# LCD_Schem.net
KiCad netlist of a schematic drawn in Altium Designer
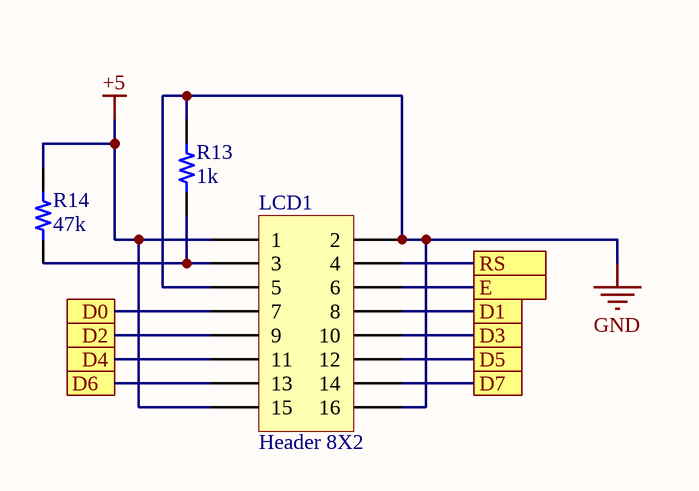
[diagram p0: LCD_Schem.SchDoc]

(export (version "E")
  (design (tool "Eeschema 10.0.6"))
  (components
    (comp (ref "LCD1")
      (value "Header 8X2")
      (footprint "HDR2X8")
      (description "Header, 8-Pin, Dual row")
      (fields (field (name "PUBLISHER") "Altium Limited"))
      (libsource (lib "Miscellaneous Connectors") (part "Header 8X2"))
    )
    (comp (ref "R13")
      (value "1k")
      (footprint "RES 1206_3216")
      (description "RES SMD 10K OHM 1% 1/2W 1206")
      (fields (field (name "PART NUMBER") "ESR18EZPF1002") (field (name "MANUFACTURER") "Rohm Semiconductor"))
      (libsource (lib "Celestial Altium Library - altium_library") (part "Resistor"))
    )
    (comp (ref "R14")
      (value "47k")
      (footprint "RES 1206_3216")
      (description "RES SMD 10K OHM 1% 1/2W 1206")
      (fields (field (name "PART NUMBER") "ESR18EZPF1002") (field (name "MANUFACTURER") "Rohm Semiconductor"))
      (libsource (lib "Celestial Altium Library - altium_library") (part "Resistor"))
    )
  )
  (nets
    (net (code "1") (name "+5") (class "Default")
      (node (ref "LCD1") (pin "1") (pinfunction "1_1") (pintype "passive"))
      (node (ref "LCD1") (pin "15") (pinfunction "15_15") (pintype "passive"))
      (node (ref "R14") (pin "2") (pinfunction "2_2") (pintype "passive"))
    )
    (net (code "2") (name "/D0") (class "Default")
      (node (ref "LCD1") (pin "7") (pinfunction "7_7") (pintype "passive"))
    )
    (net (code "3") (name "/D1") (class "Default")
      (node (ref "LCD1") (pin "8") (pinfunction "8_8") (pintype "passive"))
    )
    (net (code "4") (name "/D2") (class "Default")
      (node (ref "LCD1") (pin "9") (pinfunction "9_9") (pintype "passive"))
    )
    (net (code "5") (name "/D3") (class "Default")
      (node (ref "LCD1") (pin "10") (pinfunction "10_10") (pintype "passive"))
    )
    (net (code "6") (name "/D4") (class "Default")
      (node (ref "LCD1") (pin "11") (pinfunction "11_11") (pintype "passive"))
    )
    (net (code "7") (name "/D5") (class "Default")
      (node (ref "LCD1") (pin "12") (pinfunction "12_12") (pintype "passive"))
    )
    (net (code "8") (name "/D6") (class "Default")
      (node (ref "LCD1") (pin "13") (pinfunction "13_13") (pintype "passive"))
    )
    (net (code "9") (name "/D7") (class "Default")
      (node (ref "LCD1") (pin "14") (pinfunction "14_14") (pintype "passive"))
    )
    (net (code "10") (name "/E") (class "Default")
      (node (ref "LCD1") (pin "6") (pinfunction "6_6") (pintype "passive"))
    )
    (net (code "11") (name "/RS") (class "Default")
      (node (ref "LCD1") (pin "4") (pinfunction "4_4") (pintype "passive"))
    )
    (net (code "12") (name "GND") (class "Default")
      (node (ref "LCD1") (pin "16") (pinfunction "16_16") (pintype "passive"))
      (node (ref "LCD1") (pin "2") (pinfunction "2_2") (pintype "passive"))
      (node (ref "LCD1") (pin "5") (pinfunction "5_5") (pintype "passive"))
      (node (ref "R13") (pin "2") (pinfunction "2_2") (pintype "passive"))
    )
    (net (code "13") (name "Net-(LCD1-Pad3)") (class "Default")
      (node (ref "LCD1") (pin "3") (pinfunction "3_3") (pintype "passive"))
      (node (ref "R13") (pin "1") (pinfunction "1_1") (pintype "passive"))
      (node (ref "R14") (pin "1") (pinfunction "1_1") (pintype "passive"))
    )
  )
)
